# Controller_Board_Interface.net
KiCad netlist of a schematic drawn in Altium Designer
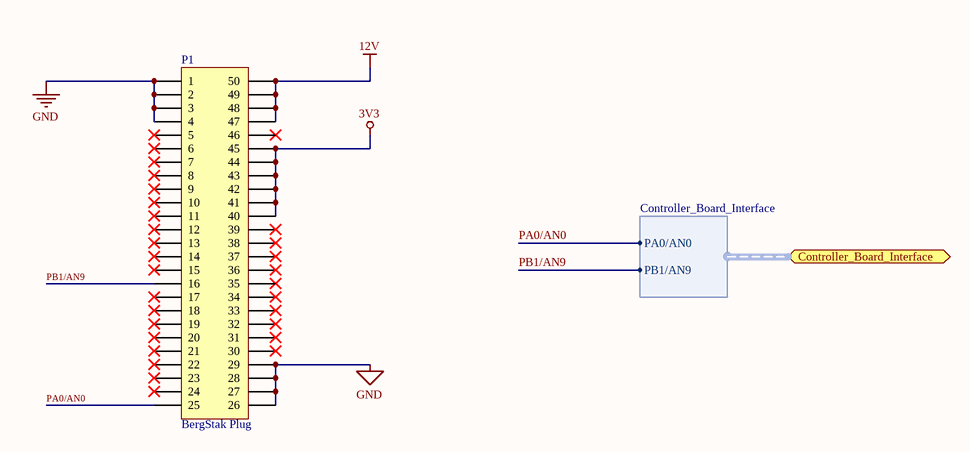
[diagram p0: Controller_Board_Interface.SchDoc]

(export (version "E")
  (design (tool "Eeschema 10.0.6"))
  (components
    (comp (ref "P1")
      (value "CONN 50POS Bergstak Plug 0.02\"")
      (footprint "CONN, Bergstak 50 Pos Plug")
      (description "50 Position Connector Plug, Outer Shroud Contacts Surface Mount Gold")
      (fields (field (name "SERIES") "BergStak Plug"))
      (libsource (lib "Schematic Diagrams") (part "CONN 50POS Bergstak Plug 0.02{dblquote}"))
    )
  )
  (nets
    (net (code "2") (name "/PA0{slash}AN0") (class "Default")
      (node (ref "P1") (pin "25") (pinfunction "25_25") (pintype "passive"))
    )
    (net (code "3") (name "/PB1{slash}AN9") (class "Default")
      (node (ref "P1") (pin "16") (pinfunction "16_16") (pintype "passive"))
    )
    (net (code "5") (name "3V3") (class "Default")
      (node (ref "P1") (pin "40") (pinfunction "40_40") (pintype "passive"))
      (node (ref "P1") (pin "41") (pinfunction "41_41") (pintype "passive"))
      (node (ref "P1") (pin "42") (pinfunction "42_42") (pintype "passive"))
      (node (ref "P1") (pin "43") (pinfunction "43_43") (pintype "passive"))
      (node (ref "P1") (pin "44") (pinfunction "44_44") (pintype "passive"))
      (node (ref "P1") (pin "45") (pinfunction "45_45") (pintype "passive"))
    )
    (net (code "6") (name "12V") (class "Default")
      (node (ref "P1") (pin "47") (pinfunction "47_47") (pintype "passive"))
      (node (ref "P1") (pin "48") (pinfunction "48_48") (pintype "passive"))
      (node (ref "P1") (pin "49") (pinfunction "49_49") (pintype "passive"))
      (node (ref "P1") (pin "50") (pinfunction "50_50") (pintype "passive"))
    )
    (net (code "7") (name "GND") (class "Default")
      (node (ref "P1") (pin "1") (pinfunction "1_1") (pintype "passive"))
      (node (ref "P1") (pin "2") (pinfunction "2_2") (pintype "passive"))
      (node (ref "P1") (pin "26") (pinfunction "26_26") (pintype "passive"))
      (node (ref "P1") (pin "27") (pinfunction "27_27") (pintype "passive"))
      (node (ref "P1") (pin "28") (pinfunction "28_28") (pintype "passive"))
      (node (ref "P1") (pin "29") (pinfunction "29_29") (pintype "passive"))
      (node (ref "P1") (pin "3") (pinfunction "3_3") (pintype "passive"))
      (node (ref "P1") (pin "4") (pinfunction "4_4") (pintype "passive"))
    )
    (net (code "8") (name "unconnected-(P1-Pad5)") (class "Default")
      (node (ref "P1") (pin "5") (pinfunction "5_5") (pintype "passive+no_connect"))
    )
    (net (code "9") (name "unconnected-(P1-Pad6)") (class "Default")
      (node (ref "P1") (pin "6") (pinfunction "6_6") (pintype "passive+no_connect"))
    )
    (net (code "10") (name "unconnected-(P1-Pad7)") (class "Default")
      (node (ref "P1") (pin "7") (pinfunction "7_7") (pintype "passive+no_connect"))
    )
    (net (code "11") (name "unconnected-(P1-Pad8)") (class "Default")
      (node (ref "P1") (pin "8") (pinfunction "8_8") (pintype "passive+no_connect"))
    )
    (net (code "12") (name "unconnected-(P1-Pad9)") (class "Default")
      (node (ref "P1") (pin "9") (pinfunction "9_9") (pintype "passive+no_connect"))
    )
    (net (code "13") (name "unconnected-(P1-Pad10)") (class "Default")
      (node (ref "P1") (pin "10") (pinfunction "10_10") (pintype "passive+no_connect"))
    )
    (net (code "14") (name "unconnected-(P1-Pad11)") (class "Default")
      (node (ref "P1") (pin "11") (pinfunction "11_11") (pintype "passive+no_connect"))
    )
    (net (code "15") (name "unconnected-(P1-Pad12)") (class "Default")
      (node (ref "P1") (pin "12") (pinfunction "12_12") (pintype "passive+no_connect"))
    )
    (net (code "16") (name "unconnected-(P1-Pad13)") (class "Default")
      (node (ref "P1") (pin "13") (pinfunction "13_13") (pintype "passive+no_connect"))
    )
    (net (code "17") (name "unconnected-(P1-Pad14)") (class "Default")
      (node (ref "P1") (pin "14") (pinfunction "14_14") (pintype "passive+no_connect"))
    )
    (net (code "18") (name "unconnected-(P1-Pad15)") (class "Default")
      (node (ref "P1") (pin "15") (pinfunction "15_15") (pintype "passive+no_connect"))
    )
    (net (code "19") (name "unconnected-(P1-Pad17)") (class "Default")
      (node (ref "P1") (pin "17") (pinfunction "17_17") (pintype "passive+no_connect"))
    )
    (net (code "20") (name "unconnected-(P1-Pad18)") (class "Default")
      (node (ref "P1") (pin "18") (pinfunction "18_18") (pintype "passive+no_connect"))
    )
    (net (code "21") (name "unconnected-(P1-Pad19)") (class "Default")
      (node (ref "P1") (pin "19") (pinfunction "19_19") (pintype "passive+no_connect"))
    )
    (net (code "22") (name "unconnected-(P1-Pad20)") (class "Default")
      (node (ref "P1") (pin "20") (pinfunction "20_20") (pintype "passive+no_connect"))
    )
    (net (code "23") (name "unconnected-(P1-Pad21)") (class "Default")
      (node (ref "P1") (pin "21") (pinfunction "21_21") (pintype "passive+no_connect"))
    )
    (net (code "24") (name "unconnected-(P1-Pad22)") (class "Default")
      (node (ref "P1") (pin "22") (pinfunction "22_22") (pintype "passive+no_connect"))
    )
    (net (code "25") (name "unconnected-(P1-Pad23)") (class "Default")
      (node (ref "P1") (pin "23") (pinfunction "23_23") (pintype "passive+no_connect"))
    )
    (net (code "26") (name "unconnected-(P1-Pad24)") (class "Default")
      (node (ref "P1") (pin "24") (pinfunction "24_24") (pintype "passive+no_connect"))
    )
    (net (code "27") (name "unconnected-(P1-Pad30)") (class "Default")
      (node (ref "P1") (pin "30") (pinfunction "30_30") (pintype "passive+no_connect"))
    )
    (net (code "28") (name "unconnected-(P1-Pad31)") (class "Default")
      (node (ref "P1") (pin "31") (pinfunction "31_31") (pintype "passive+no_connect"))
    )
    (net (code "29") (name "unconnected-(P1-Pad32)") (class "Default")
      (node (ref "P1") (pin "32") (pinfunction "32_32") (pintype "passive+no_connect"))
    )
    (net (code "30") (name "unconnected-(P1-Pad33)") (class "Default")
      (node (ref "P1") (pin "33") (pinfunction "33_33") (pintype "passive+no_connect"))
    )
    (net (code "31") (name "unconnected-(P1-Pad34)") (class "Default")
      (node (ref "P1") (pin "34") (pinfunction "34_34") (pintype "passive+no_connect"))
    )
    (net (code "32") (name "unconnected-(P1-Pad35)") (class "Default")
      (node (ref "P1") (pin "35") (pinfunction "35_35") (pintype "passive+no_connect"))
    )
    (net (code "33") (name "unconnected-(P1-Pad36)") (class "Default")
      (node (ref "P1") (pin "36") (pinfunction "36_36") (pintype "passive+no_connect"))
    )
    (net (code "34") (name "unconnected-(P1-Pad37)") (class "Default")
      (node (ref "P1") (pin "37") (pinfunction "37_37") (pintype "passive+no_connect"))
    )
    (net (code "35") (name "unconnected-(P1-Pad38)") (class "Default")
      (node (ref "P1") (pin "38") (pinfunction "38_38") (pintype "passive+no_connect"))
    )
    (net (code "36") (name "unconnected-(P1-Pad39)") (class "Default")
      (node (ref "P1") (pin "39") (pinfunction "39_39") (pintype "passive+no_connect"))
    )
    (net (code "37") (name "unconnected-(P1-Pad46)") (class "Default")
      (node (ref "P1") (pin "46") (pinfunction "46_46") (pintype "passive+no_connect"))
    )
  )
)
